# ArduinoBase.net
KiCad netlist of a schematic drawn in EAGLE
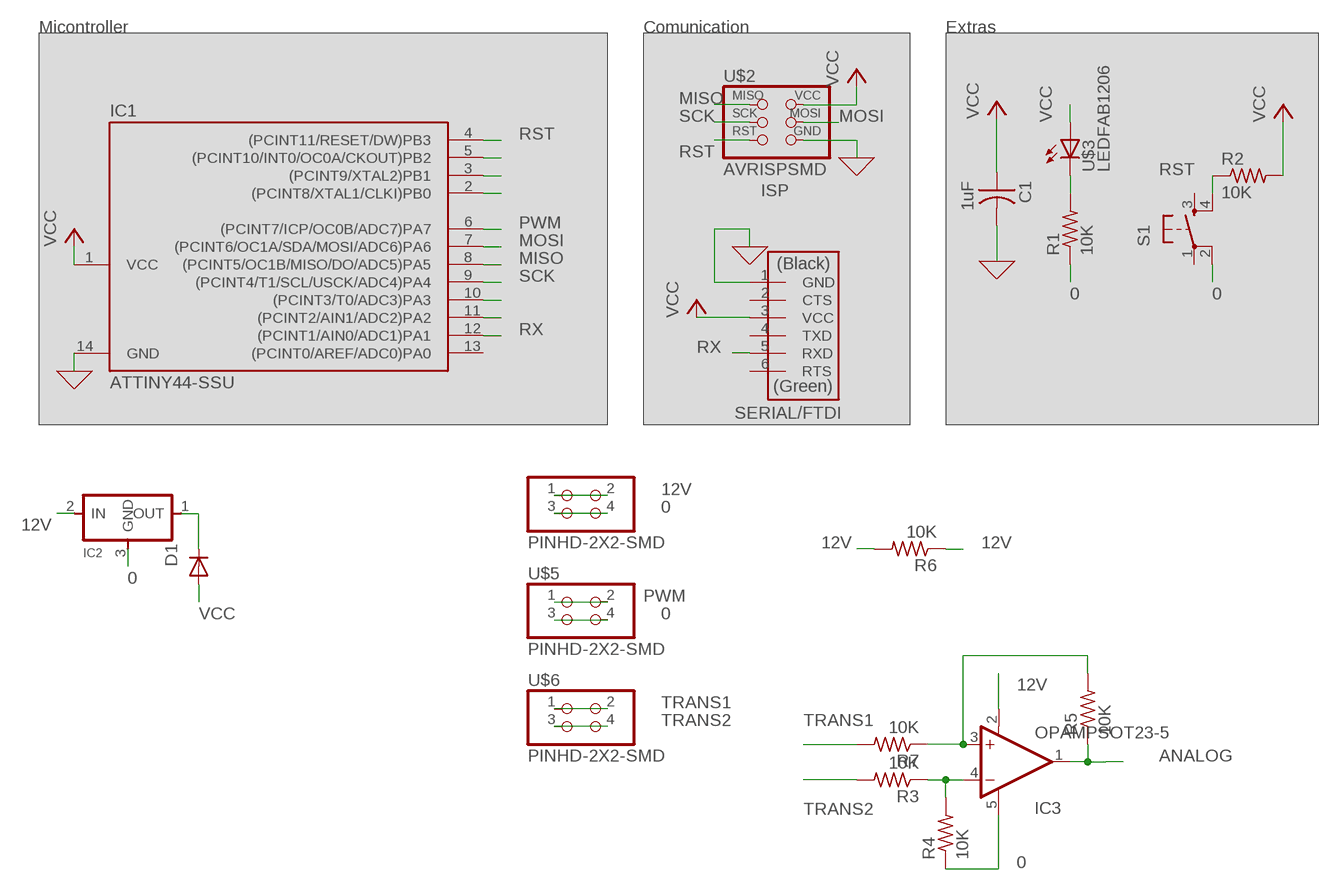
[diagram p0: schematic, sheet 1]

(export (version "E")
  (design (tool "Eeschema 10.0.6"))
  (components
    (comp (ref "C1")
      (value "1uF")
      (footprint "eagle-import:C1206FAB")
      (libsource (lib "eagle-import") (part "CAP-US1206FAB"))
    )
    (comp (ref "D1")
      (value "DIODESOD123")
      (footprint "eagle-import:SOD123")
      (libsource (lib "eagle-import") (part "DIODESOD123"))
    )
    (comp (ref "GND")
      (value "PINHD-2X2-SMD")
      (footprint "eagle-import:2X02SMD")
      (libsource (lib "eagle-import") (part "PINHD-2X2-SMD"))
    )
    (comp (ref "IC1")
      (value "ATTINY44-SSU")
      (footprint "eagle-import:SOIC14")
      (libsource (lib "eagle-import") (part "ATTINY44-SSU"))
    )
    (comp (ref "IC2")
      (value "REGULATORSOT23")
      (footprint "eagle-import:SOT23")
      (libsource (lib "eagle-import") (part "REGULATORSOT23"))
    )
    (comp (ref "IC3")
      (value "OPAMPSOT23-5")
      (footprint "eagle-import:SOT23-5")
      (libsource (lib "eagle-import") (part "OPAMPSOT23-5"))
    )
    (comp (ref "R1")
      (value "10K")
      (footprint "eagle-import:R1206FAB")
      (libsource (lib "eagle-import") (part "RES-US1206FAB"))
    )
    (comp (ref "R2")
      (value "10K")
      (footprint "eagle-import:R1206FAB")
      (libsource (lib "eagle-import") (part "RES-US1206FAB"))
    )
    (comp (ref "R3")
      (value "10K")
      (footprint "eagle-import:R1206FAB")
      (libsource (lib "eagle-import") (part "RES-US1206FAB"))
    )
    (comp (ref "R4")
      (value "10K")
      (footprint "eagle-import:R1206FAB")
      (libsource (lib "eagle-import") (part "RES-US1206FAB"))
    )
    (comp (ref "R5")
      (value "10K")
      (footprint "eagle-import:R1206FAB")
      (libsource (lib "eagle-import") (part "RES-US1206FAB"))
    )
    (comp (ref "R6")
      (value "10K")
      (footprint "eagle-import:R1206FAB")
      (libsource (lib "eagle-import") (part "RES-US1206FAB"))
    )
    (comp (ref "R7")
      (value "10K")
      (footprint "eagle-import:R1206FAB")
      (libsource (lib "eagle-import") (part "RES-US1206FAB"))
    )
    (comp (ref "S1")
      (value "6MM_SWITCH6MM_SWITCH")
      (footprint "eagle-import:6MM_SWITCH")
      (libsource (lib "eagle-import") (part "6MM_SWITCH6MM_SWITCH"))
    )
    (comp (ref "U$1")
      (value "FTDI-SMD-HEADER")
      (footprint "eagle-import:1X06SMD")
      (libsource (lib "eagle-import") (part "FTDI-SMD-HEADER"))
    )
    (comp (ref "U$2")
      (value "AVRISPSMD")
      (footprint "eagle-import:2X03SMD")
      (libsource (lib "eagle-import") (part "AVRISPSMD"))
    )
    (comp (ref "U$3")
      (value "LEDFAB1206")
      (footprint "eagle-import:LED1206FAB")
      (libsource (lib "eagle-import") (part "LEDFAB1206"))
    )
    (comp (ref "U$5")
      (value "PINHD-2X2-SMD")
      (footprint "eagle-import:2X02SMD")
      (libsource (lib "eagle-import") (part "PINHD-2X2-SMD"))
    )
    (comp (ref "U$6")
      (value "PINHD-2X2-SMD")
      (footprint "eagle-import:2X02SMD")
      (libsource (lib "eagle-import") (part "PINHD-2X2-SMD"))
    )
  )
  (nets
    (net (code "1") (name "/12V") (class "Default")
      (node (ref "GND") (pin "1") (pinfunction "1_1") (pintype "passive"))
      (node (ref "GND") (pin "2") (pinfunction "2_2") (pintype "passive"))
      (node (ref "IC2") (pin "2") (pinfunction "IN_2") (pintype "bidirectional"))
      (node (ref "IC3") (pin "2") (pinfunction "V-_2") (pintype "power_in"))
      (node (ref "R6") (pin "1") (pinfunction "1_1") (pintype "passive"))
      (node (ref "R6") (pin "2") (pinfunction "2_2") (pintype "passive"))
    )
    (net (code "2") (name "/ANALOG") (class "Default")
      (node (ref "IC3") (pin "1") (pinfunction "OUT_1") (pintype "output"))
      (node (ref "R5") (pin "1") (pinfunction "1_1") (pintype "passive"))
    )
    (net (code "3") (name "/MISO") (class "Default")
      (node (ref "IC1") (pin "8") (pinfunction "(PCINT5/OC1B/MISO/DO/ADC5)PA5_8") (pintype "bidirectional"))
      (node (ref "U$2") (pin "1") (pinfunction "MISO_1") (pintype "passive"))
    )
    (net (code "4") (name "/MOSI") (class "Default")
      (node (ref "IC1") (pin "7") (pinfunction "(PCINT6/OC1A/SDA/MOSI/ADC6)PA6_7") (pintype "bidirectional"))
      (node (ref "U$2") (pin "4") (pinfunction "MOSI_4") (pintype "passive"))
    )
    (net (code "5") (name "/PWM") (class "Default")
      (node (ref "IC1") (pin "6") (pinfunction "(PCINT7/ICP/OC0B/ADC7)PA7_6") (pintype "bidirectional"))
      (node (ref "U$5") (pin "1") (pinfunction "1_1") (pintype "passive"))
      (node (ref "U$5") (pin "2") (pinfunction "2_2") (pintype "passive"))
    )
    (net (code "6") (name "/RST") (class "Default")
      (node (ref "IC1") (pin "4") (pinfunction "(PCINT11/RESET/DW)PB3_4") (pintype "bidirectional"))
      (node (ref "R2") (pin "1") (pinfunction "1_1") (pintype "passive"))
      (node (ref "S1") (pin "4") (pinfunction "S1_4") (pintype "passive"))
      (node (ref "U$2") (pin "5") (pinfunction "RST_5") (pintype "passive"))
    )
    (net (code "7") (name "/RX") (class "Default")
      (node (ref "IC1") (pin "12") (pinfunction "(PCINT1/AIN0/ADC1)PA1_12") (pintype "bidirectional"))
      (node (ref "U$1") (pin "5") (pinfunction "RXD_5") (pintype "bidirectional"))
    )
    (net (code "8") (name "/SCK") (class "Default")
      (node (ref "IC1") (pin "9") (pinfunction "(PCINT4/T1/SCL/USCK/ADC4)PA4_9") (pintype "bidirectional"))
      (node (ref "U$2") (pin "3") (pinfunction "SCK_3") (pintype "passive"))
    )
    (net (code "9") (name "/TRANS1") (class "Default")
      (node (ref "R7") (pin "2") (pinfunction "2_2") (pintype "passive"))
      (node (ref "U$6") (pin "1") (pinfunction "1_1") (pintype "passive"))
      (node (ref "U$6") (pin "2") (pinfunction "2_2") (pintype "passive"))
    )
    (net (code "10") (name "/TRANS2") (class "Default")
      (node (ref "R3") (pin "2") (pinfunction "2_2") (pintype "passive"))
      (node (ref "U$6") (pin "3") (pinfunction "3_3") (pintype "passive"))
      (node (ref "U$6") (pin "4") (pinfunction "4_4") (pintype "passive"))
    )
    (net (code "11") (name "GND") (class "Default")
      (node (ref "C1") (pin "2") (pinfunction "2_2") (pintype "passive"))
      (node (ref "GND") (pin "3") (pinfunction "3_3") (pintype "passive"))
      (node (ref "GND") (pin "4") (pinfunction "4_4") (pintype "passive"))
      (node (ref "IC1") (pin "14") (pinfunction "GND_14") (pintype "power_in"))
      (node (ref "IC2") (pin "3") (pinfunction "GND_3") (pintype "bidirectional"))
      (node (ref "IC3") (pin "5") (pinfunction "V+_5") (pintype "power_in"))
      (node (ref "R1") (pin "1") (pinfunction "1_1") (pintype "passive"))
      (node (ref "R4") (pin "1") (pinfunction "1_1") (pintype "passive"))
      (node (ref "S1") (pin "2") (pinfunction "P1_2") (pintype "passive"))
      (node (ref "U$1") (pin "1") (pinfunction "GND_1") (pintype "bidirectional"))
      (node (ref "U$2") (pin "6") (pinfunction "GND_6") (pintype "passive"))
      (node (ref "U$5") (pin "3") (pinfunction "3_3") (pintype "passive"))
      (node (ref "U$5") (pin "4") (pinfunction "4_4") (pintype "passive"))
    )
    (net (code "12") (name "Net-(D1-C)") (class "Default")
      (node (ref "D1") (pin "CATHODE") (pinfunction "C_CATHODE") (pintype "passive"))
      (node (ref "IC2") (pin "1") (pinfunction "OUT_1") (pintype "bidirectional"))
    )
    (net (code "13") (name "Net-(IC3-+IN)") (class "Default")
      (node (ref "IC3") (pin "3") (pinfunction "+IN_3") (pintype "input"))
      (node (ref "R5") (pin "2") (pinfunction "2_2") (pintype "passive"))
      (node (ref "R7") (pin "1") (pinfunction "1_1") (pintype "passive"))
    )
    (net (code "14") (name "Net-(IC3--IN)") (class "Default")
      (node (ref "IC3") (pin "4") (pinfunction "-IN_4") (pintype "input"))
      (node (ref "R3") (pin "1") (pinfunction "1_1") (pintype "passive"))
      (node (ref "R4") (pin "2") (pinfunction "2_2") (pintype "passive"))
    )
    (net (code "15") (name "Net-(U$3-C)") (class "Default")
      (node (ref "R1") (pin "2") (pinfunction "2_2") (pintype "passive"))
      (node (ref "U$3") (pin "2") (pinfunction "C_2") (pintype "passive"))
    )
    (net (code "16") (name "VCC") (class "Default")
      (node (ref "C1") (pin "1") (pinfunction "1_1") (pintype "passive"))
      (node (ref "D1") (pin "ANODE") (pinfunction "A_ANODE") (pintype "passive"))
      (node (ref "IC1") (pin "1") (pinfunction "VCC_1") (pintype "power_in"))
      (node (ref "R2") (pin "2") (pinfunction "2_2") (pintype "passive"))
      (node (ref "U$1") (pin "3") (pinfunction "VCC_3") (pintype "bidirectional"))
      (node (ref "U$2") (pin "2") (pinfunction "VCC_2") (pintype "passive"))
      (node (ref "U$3") (pin "1") (pinfunction "A_1") (pintype "passive"))
    )
    (net (code "17") (name "unconnected-(IC1-(PCINT0{slash}AREF{slash}ADC0)PA0-Pad13)") (class "Default")
      (node (ref "IC1") (pin "13") (pinfunction "(PCINT0/AREF/ADC0)PA0_13") (pintype "bidirectional"))
    )
    (net (code "18") (name "unconnected-(IC1-(PCINT2{slash}AIN1{slash}ADC2)PA2-Pad11)") (class "Default")
      (node (ref "IC1") (pin "11") (pinfunction "(PCINT2/AIN1/ADC2)PA2_11") (pintype "bidirectional"))
    )
    (net (code "19") (name "unconnected-(IC1-(PCINT3{slash}T0{slash}ADC3)PA3-Pad10)") (class "Default")
      (node (ref "IC1") (pin "10") (pinfunction "(PCINT3/T0/ADC3)PA3_10") (pintype "bidirectional"))
    )
    (net (code "20") (name "unconnected-(IC1-(PCINT8{slash}XTAL1{slash}CLKI)PB0-Pad2)") (class "Default")
      (node (ref "IC1") (pin "2") (pinfunction "(PCINT8/XTAL1/CLKI)PB0_2") (pintype "bidirectional"))
    )
    (net (code "21") (name "unconnected-(IC1-(PCINT9{slash}XTAL2)PB1-Pad3)") (class "Default")
      (node (ref "IC1") (pin "3") (pinfunction "(PCINT9/XTAL2)PB1_3") (pintype "bidirectional"))
    )
    (net (code "22") (name "unconnected-(IC1-(PCINT10{slash}INT0{slash}OC0A{slash}CKOUT)PB2-Pad5)") (class "Default")
      (node (ref "IC1") (pin "5") (pinfunction "(PCINT10/INT0/OC0A/CKOUT)PB2_5") (pintype "bidirectional"))
    )
    (net (code "23") (name "unconnected-(S1-P-Pad1)") (class "Default")
      (node (ref "S1") (pin "1") (pinfunction "P_1") (pintype "passive"))
    )
    (net (code "24") (name "unconnected-(S1-S-Pad3)") (class "Default")
      (node (ref "S1") (pin "3") (pinfunction "S_3") (pintype "passive"))
    )
    (net (code "25") (name "unconnected-(U$1-CTS-Pad2)") (class "Default")
      (node (ref "U$1") (pin "2") (pinfunction "CTS_2") (pintype "bidirectional"))
    )
    (net (code "26") (name "unconnected-(U$1-RTS-Pad6)") (class "Default")
      (node (ref "U$1") (pin "6") (pinfunction "RTS_6") (pintype "bidirectional"))
    )
    (net (code "27") (name "unconnected-(U$1-TXD-Pad4)") (class "Default")
      (node (ref "U$1") (pin "4") (pinfunction "TXD_4") (pintype "bidirectional"))
    )
  )
)
